# 12v_Outputs.net
KiCad netlist of a schematic drawn in Altium Designer
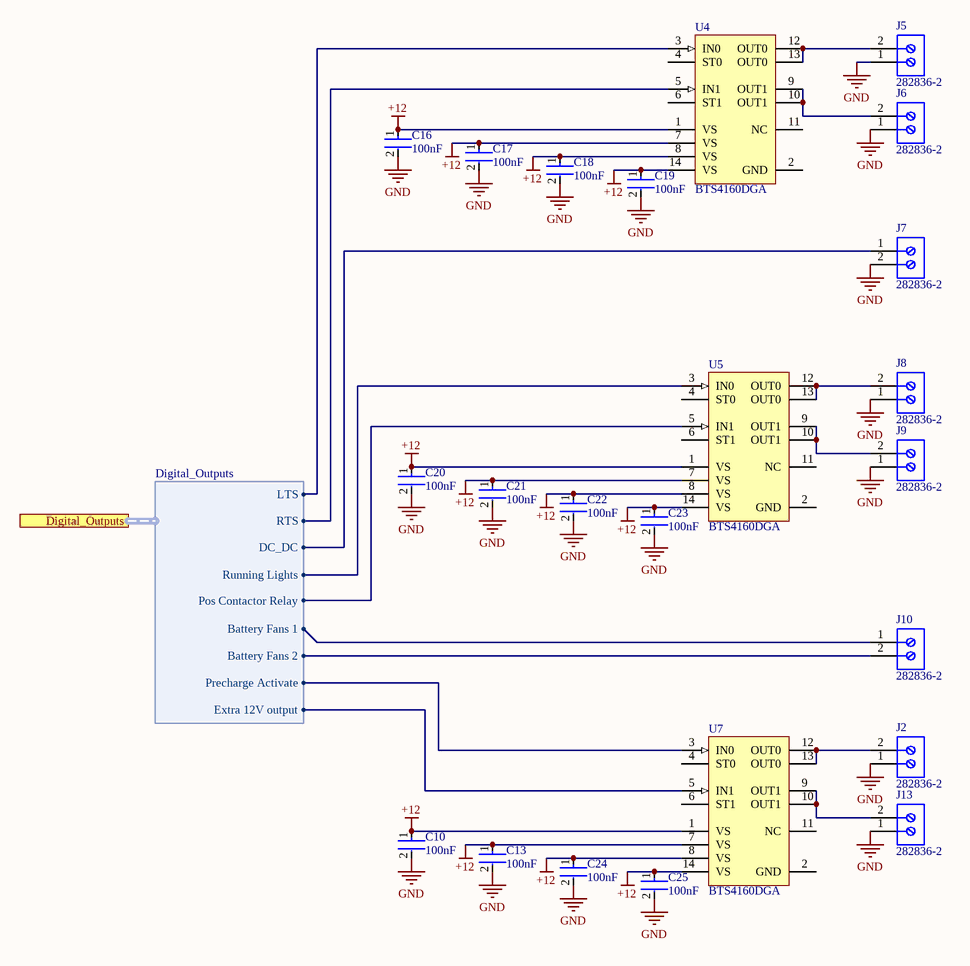
[diagram p0: 12v_Outputs.SchDoc]

(export (version "E")
  (design (tool "Eeschema 10.0.6"))
  (components
    (comp (ref "C10")
      (value "100nF")
      (footprint "Kemet_C0603_IPC_A")
      (description "CAP CER 0.1UF 100NF 50V X7R 0603 C0603C104K5RACTU")
      (libsource (lib "UNK_Kemet_C0603C104K5RACTU_eec") (part "C0603C104K5RACTU"))
    )
    (comp (ref "C13")
      (value "100nF")
      (footprint "Kemet_C0603_IPC_A")
      (description "CAP CER 0.1UF 100NF 50V X7R 0603 C0603C104K5RACTU")
      (libsource (lib "UNK_Kemet_C0603C104K5RACTU_eec") (part "C0603C104K5RACTU"))
    )
    (comp (ref "C16")
      (value "100nF")
      (footprint "Kemet_C0603_IPC_A")
      (description "CAP CER 0.1UF 100NF 50V X7R 0603 C0603C104K5RACTU")
      (libsource (lib "UNK_Kemet_C0603C104K5RACTU_eec") (part "C0603C104K5RACTU"))
    )
    (comp (ref "C17")
      (value "100nF")
      (footprint "Kemet_C0603_IPC_A")
      (description "CAP CER 0.1UF 100NF 50V X7R 0603 C0603C104K5RACTU")
      (libsource (lib "UNK_Kemet_C0603C104K5RACTU_eec") (part "C0603C104K5RACTU"))
    )
    (comp (ref "C18")
      (value "100nF")
      (footprint "Kemet_C0603_IPC_A")
      (description "CAP CER 0.1UF 100NF 50V X7R 0603 C0603C104K5RACTU")
      (libsource (lib "UNK_Kemet_C0603C104K5RACTU_eec") (part "C0603C104K5RACTU"))
    )
    (comp (ref "C19")
      (value "100nF")
      (footprint "Kemet_C0603_IPC_A")
      (description "CAP CER 0.1UF 100NF 50V X7R 0603 C0603C104K5RACTU")
      (libsource (lib "UNK_Kemet_C0603C104K5RACTU_eec") (part "C0603C104K5RACTU"))
    )
    (comp (ref "C20")
      (value "100nF")
      (footprint "Kemet_C0603_IPC_A")
      (description "CAP CER 0.1UF 100NF 50V X7R 0603 C0603C104K5RACTU")
      (libsource (lib "UNK_Kemet_C0603C104K5RACTU_eec") (part "C0603C104K5RACTU"))
    )
    (comp (ref "C21")
      (value "100nF")
      (footprint "Kemet_C0603_IPC_A")
      (description "CAP CER 0.1UF 100NF 50V X7R 0603 C0603C104K5RACTU")
      (libsource (lib "UNK_Kemet_C0603C104K5RACTU_eec") (part "C0603C104K5RACTU"))
    )
    (comp (ref "C22")
      (value "100nF")
      (footprint "Kemet_C0603_IPC_A")
      (description "CAP CER 0.1UF 100NF 50V X7R 0603 C0603C104K5RACTU")
      (libsource (lib "UNK_Kemet_C0603C104K5RACTU_eec") (part "C0603C104K5RACTU"))
    )
    (comp (ref "C23")
      (value "100nF")
      (footprint "Kemet_C0603_IPC_A")
      (description "CAP CER 0.1UF 100NF 50V X7R 0603 C0603C104K5RACTU")
      (libsource (lib "UNK_Kemet_C0603C104K5RACTU_eec") (part "C0603C104K5RACTU"))
    )
    (comp (ref "C24")
      (value "100nF")
      (footprint "Kemet_C0603_IPC_A")
      (description "CAP CER 0.1UF 100NF 50V X7R 0603 C0603C104K5RACTU")
      (libsource (lib "UNK_Kemet_C0603C104K5RACTU_eec") (part "C0603C104K5RACTU"))
    )
    (comp (ref "C25")
      (value "100nF")
      (footprint "Kemet_C0603_IPC_A")
      (description "CAP CER 0.1UF 100NF 50V X7R 0603 C0603C104K5RACTU")
      (libsource (lib "UNK_Kemet_C0603C104K5RACTU_eec") (part "C0603C104K5RACTU"))
    )
    (comp (ref "J2")
      (value "282836-2")
      (footprint "TECO-282836-2_V")
      (description "Female Header, Pitch 5 mm, 1 x 2 Position, Height 10 mm, Tail Length 3.5 mm, Rohs, Bulk")
      (fields (field (name "VOLTAGE") "300V") (field (name "MANUFACTURER") "TE Connectivity"))
      (libsource (lib "Altium Content Vault") (part "CN-1P-F-TB2"))
    )
    (comp (ref "J5")
      (value "282836-2")
      (footprint "TECO-282836-2_V")
      (description "Female Header, Pitch 5 mm, 1 x 2 Position, Height 10 mm, Tail Length 3.5 mm, Rohs, Bulk")
      (fields (field (name "VOLTAGE") "300V") (field (name "MANUFACTURER") "TE Connectivity"))
      (libsource (lib "Altium Content Vault") (part "CN-1P-F-TB2"))
    )
    (comp (ref "J6")
      (value "282836-2")
      (footprint "TECO-282836-2_V")
      (description "Female Header, Pitch 5 mm, 1 x 2 Position, Height 10 mm, Tail Length 3.5 mm, Rohs, Bulk")
      (fields (field (name "VOLTAGE") "300V") (field (name "MANUFACTURER") "TE Connectivity"))
      (libsource (lib "Altium Content Vault") (part "CN-1P-F-TB2"))
    )
    (comp (ref "J7")
      (value "282836-2")
      (footprint "TECO-282836-2_V")
      (description "Female Header, Pitch 5 mm, 1 x 2 Position, Height 10 mm, Tail Length 3.5 mm, Rohs, Bulk")
      (fields (field (name "VOLTAGE") "300V") (field (name "MANUFACTURER") "TE Connectivity"))
      (libsource (lib "Altium Content Vault") (part "CN-1P-F-TB2"))
    )
    (comp (ref "J8")
      (value "282836-2")
      (footprint "TECO-282836-2_V")
      (description "Female Header, Pitch 5 mm, 1 x 2 Position, Height 10 mm, Tail Length 3.5 mm, Rohs, Bulk")
      (fields (field (name "VOLTAGE") "300V") (field (name "MANUFACTURER") "TE Connectivity"))
      (libsource (lib "Altium Content Vault") (part "CN-1P-F-TB2"))
    )
    (comp (ref "J9")
      (value "282836-2")
      (footprint "TECO-282836-2_V")
      (description "Female Header, Pitch 5 mm, 1 x 2 Position, Height 10 mm, Tail Length 3.5 mm, Rohs, Bulk")
      (fields (field (name "VOLTAGE") "300V") (field (name "MANUFACTURER") "TE Connectivity"))
      (libsource (lib "Altium Content Vault") (part "CN-1P-F-TB2"))
    )
    (comp (ref "J10")
      (value "282836-2")
      (footprint "TECO-282836-2_V")
      (description "Female Header, Pitch 5 mm, 1 x 2 Position, Height 10 mm, Tail Length 3.5 mm, Rohs, Bulk")
      (fields (field (name "VOLTAGE") "300V") (field (name "MANUFACTURER") "TE Connectivity"))
      (libsource (lib "Altium Content Vault") (part "CN-1P-F-TB2"))
    )
    (comp (ref "J13")
      (value "282836-2")
      (footprint "TECO-282836-2_V")
      (description "Female Header, Pitch 5 mm, 1 x 2 Position, Height 10 mm, Tail Length 3.5 mm, Rohs, Bulk")
      (fields (field (name "VOLTAGE") "300V") (field (name "MANUFACTURER") "TE Connectivity"))
      (libsource (lib "Altium Content Vault") (part "CN-1P-F-TB2"))
    )
    (comp (ref "U4")
      (value "BTS4160DGA")
      (footprint "INF-PG-DSO-14-37_N")
      (fields (field (name "MANUFACTURER") "Infineon"))
      (libsource (lib "Infineon_BTS4160DGA") (part "BTS4160DGA"))
    )
    (comp (ref "U5")
      (value "BTS4160DGA")
      (footprint "INF-PG-DSO-14-37_N")
      (fields (field (name "MANUFACTURER") "Infineon"))
      (libsource (lib "Infineon_BTS4160DGA") (part "BTS4160DGA"))
    )
    (comp (ref "U7")
      (value "BTS4160DGA")
      (footprint "INF-PG-DSO-14-37_N")
      (fields (field (name "MANUFACTURER") "Infineon"))
      (libsource (lib "Infineon_BTS4160DGA") (part "BTS4160DGA"))
    )
  )
  (nets
    (net (code "2") (name "+12") (class "Default")
      (node (ref "C10") (pin "1") (pinfunction "1_1") (pintype "passive"))
      (node (ref "C13") (pin "1") (pinfunction "1_1") (pintype "passive"))
      (node (ref "C16") (pin "1") (pinfunction "1_1") (pintype "passive"))
      (node (ref "C17") (pin "1") (pinfunction "1_1") (pintype "passive"))
      (node (ref "C18") (pin "1") (pinfunction "1_1") (pintype "passive"))
      (node (ref "C19") (pin "1") (pinfunction "1_1") (pintype "passive"))
      (node (ref "C20") (pin "1") (pinfunction "1_1") (pintype "passive"))
      (node (ref "C21") (pin "1") (pinfunction "1_1") (pintype "passive"))
      (node (ref "C22") (pin "1") (pinfunction "1_1") (pintype "passive"))
      (node (ref "C23") (pin "1") (pinfunction "1_1") (pintype "passive"))
      (node (ref "C24") (pin "1") (pinfunction "1_1") (pintype "passive"))
      (node (ref "C25") (pin "1") (pinfunction "1_1") (pintype "passive"))
      (node (ref "U4") (pin "1") (pinfunction "VS_1") (pintype "power_in"))
      (node (ref "U4") (pin "14") (pinfunction "VS_14") (pintype "power_in"))
      (node (ref "U4") (pin "7") (pinfunction "VS_7") (pintype "power_in"))
      (node (ref "U4") (pin "8") (pinfunction "VS_8") (pintype "power_in"))
      (node (ref "U5") (pin "1") (pinfunction "VS_1") (pintype "power_in"))
      (node (ref "U5") (pin "14") (pinfunction "VS_14") (pintype "power_in"))
      (node (ref "U5") (pin "7") (pinfunction "VS_7") (pintype "power_in"))
      (node (ref "U5") (pin "8") (pinfunction "VS_8") (pintype "power_in"))
      (node (ref "U7") (pin "1") (pinfunction "VS_1") (pintype "power_in"))
      (node (ref "U7") (pin "14") (pinfunction "VS_14") (pintype "power_in"))
      (node (ref "U7") (pin "7") (pinfunction "VS_7") (pintype "power_in"))
      (node (ref "U7") (pin "8") (pinfunction "VS_8") (pintype "power_in"))
    )
    (net (code "3") (name "/Battery Fans 1") (class "Default")
      (node (ref "J10") (pin "1") (pinfunction "1_1") (pintype "passive"))
    )
    (net (code "4") (name "/Battery Fans 2") (class "Default")
      (node (ref "J10") (pin "2") (pinfunction "2_2") (pintype "passive"))
    )
    (net (code "5") (name "/DC_DC") (class "Default")
      (node (ref "J7") (pin "1") (pinfunction "1_1") (pintype "passive"))
    )
    (net (code "6") (name "/Extra 12V output") (class "Default")
      (node (ref "U7") (pin "5") (pinfunction "IN1_5") (pintype "input"))
    )
    (net (code "7") (name "/LTS") (class "Default")
      (node (ref "U4") (pin "3") (pinfunction "IN0_3") (pintype "input"))
    )
    (net (code "8") (name "/Pos Contactor Relay") (class "Default")
      (node (ref "U5") (pin "5") (pinfunction "IN1_5") (pintype "input"))
    )
    (net (code "9") (name "/Precharge Activate") (class "Default")
      (node (ref "U7") (pin "3") (pinfunction "IN0_3") (pintype "input"))
    )
    (net (code "10") (name "/RTS") (class "Default")
      (node (ref "U4") (pin "5") (pinfunction "IN1_5") (pintype "input"))
    )
    (net (code "11") (name "/Running Lights") (class "Default")
      (node (ref "U5") (pin "3") (pinfunction "IN0_3") (pintype "input"))
    )
    (net (code "13") (name "GND") (class "Default")
      (node (ref "C10") (pin "2") (pinfunction "2_2") (pintype "passive"))
      (node (ref "C13") (pin "2") (pinfunction "2_2") (pintype "passive"))
      (node (ref "C16") (pin "2") (pinfunction "2_2") (pintype "passive"))
      (node (ref "C17") (pin "2") (pinfunction "2_2") (pintype "passive"))
      (node (ref "C18") (pin "2") (pinfunction "2_2") (pintype "passive"))
      (node (ref "C19") (pin "2") (pinfunction "2_2") (pintype "passive"))
      (node (ref "C20") (pin "2") (pinfunction "2_2") (pintype "passive"))
      (node (ref "C21") (pin "2") (pinfunction "2_2") (pintype "passive"))
      (node (ref "C22") (pin "2") (pinfunction "2_2") (pintype "passive"))
      (node (ref "C23") (pin "2") (pinfunction "2_2") (pintype "passive"))
      (node (ref "C24") (pin "2") (pinfunction "2_2") (pintype "passive"))
      (node (ref "C25") (pin "2") (pinfunction "2_2") (pintype "passive"))
      (node (ref "J13") (pin "1") (pinfunction "1_1") (pintype "passive"))
      (node (ref "J2") (pin "1") (pinfunction "1_1") (pintype "passive"))
      (node (ref "J5") (pin "1") (pinfunction "1_1") (pintype "passive"))
      (node (ref "J6") (pin "1") (pinfunction "1_1") (pintype "passive"))
      (node (ref "J7") (pin "2") (pinfunction "2_2") (pintype "passive"))
      (node (ref "J8") (pin "1") (pinfunction "1_1") (pintype "passive"))
      (node (ref "J9") (pin "1") (pinfunction "1_1") (pintype "passive"))
    )
    (net (code "14") (name "Net-(J2-Pad2)") (class "Default")
      (node (ref "J2") (pin "2") (pinfunction "2_2") (pintype "passive"))
      (node (ref "U7") (pin "12") (pinfunction "OUT0_12") (pintype "power_in"))
      (node (ref "U7") (pin "13") (pinfunction "OUT0_13") (pintype "power_in"))
    )
    (net (code "15") (name "Net-(J5-Pad2)") (class "Default")
      (node (ref "J5") (pin "2") (pinfunction "2_2") (pintype "passive"))
      (node (ref "U4") (pin "12") (pinfunction "OUT0_12") (pintype "power_in"))
      (node (ref "U4") (pin "13") (pinfunction "OUT0_13") (pintype "power_in"))
    )
    (net (code "16") (name "Net-(J6-Pad2)") (class "Default")
      (node (ref "J6") (pin "2") (pinfunction "2_2") (pintype "passive"))
      (node (ref "U4") (pin "10") (pinfunction "OUT1_10") (pintype "power_in"))
      (node (ref "U4") (pin "9") (pinfunction "OUT1_9") (pintype "power_in"))
    )
    (net (code "17") (name "Net-(J8-Pad2)") (class "Default")
      (node (ref "J8") (pin "2") (pinfunction "2_2") (pintype "passive"))
      (node (ref "U5") (pin "12") (pinfunction "OUT0_12") (pintype "power_in"))
      (node (ref "U5") (pin "13") (pinfunction "OUT0_13") (pintype "power_in"))
    )
    (net (code "18") (name "Net-(J9-Pad2)") (class "Default")
      (node (ref "J9") (pin "2") (pinfunction "2_2") (pintype "passive"))
      (node (ref "U5") (pin "10") (pinfunction "OUT1_10") (pintype "power_in"))
      (node (ref "U5") (pin "9") (pinfunction "OUT1_9") (pintype "power_in"))
    )
    (net (code "19") (name "Net-(J13-Pad2)") (class "Default")
      (node (ref "J13") (pin "2") (pinfunction "2_2") (pintype "passive"))
      (node (ref "U7") (pin "10") (pinfunction "OUT1_10") (pintype "power_in"))
      (node (ref "U7") (pin "9") (pinfunction "OUT1_9") (pintype "power_in"))
    )
    (net (code "20") (name "unconnected-(U4-GND-Pad2)") (class "Default")
      (node (ref "U4") (pin "2") (pinfunction "GND_2") (pintype "power_in"))
    )
    (net (code "21") (name "unconnected-(U4-NC-Pad11)") (class "Default")
      (node (ref "U4") (pin "11") (pinfunction "NC_11") (pintype "passive"))
    )
    (net (code "22") (name "unconnected-(U4-ST0-Pad4)") (class "Default")
      (node (ref "U4") (pin "4") (pinfunction "ST0_4") (pintype "open_collector"))
    )
    (net (code "23") (name "unconnected-(U4-ST1-Pad6)") (class "Default")
      (node (ref "U4") (pin "6") (pinfunction "ST1_6") (pintype "open_collector"))
    )
    (net (code "24") (name "unconnected-(U5-GND-Pad2)") (class "Default")
      (node (ref "U5") (pin "2") (pinfunction "GND_2") (pintype "power_in"))
    )
    (net (code "25") (name "unconnected-(U5-NC-Pad11)") (class "Default")
      (node (ref "U5") (pin "11") (pinfunction "NC_11") (pintype "passive"))
    )
    (net (code "26") (name "unconnected-(U5-ST0-Pad4)") (class "Default")
      (node (ref "U5") (pin "4") (pinfunction "ST0_4") (pintype "open_collector"))
    )
    (net (code "27") (name "unconnected-(U5-ST1-Pad6)") (class "Default")
      (node (ref "U5") (pin "6") (pinfunction "ST1_6") (pintype "open_collector"))
    )
    (net (code "28") (name "unconnected-(U7-GND-Pad2)") (class "Default")
      (node (ref "U7") (pin "2") (pinfunction "GND_2") (pintype "power_in"))
    )
    (net (code "29") (name "unconnected-(U7-NC-Pad11)") (class "Default")
      (node (ref "U7") (pin "11") (pinfunction "NC_11") (pintype "passive"))
    )
    (net (code "30") (name "unconnected-(U7-ST0-Pad4)") (class "Default")
      (node (ref "U7") (pin "4") (pinfunction "ST0_4") (pintype "open_collector"))
    )
    (net (code "31") (name "unconnected-(U7-ST1-Pad6)") (class "Default")
      (node (ref "U7") (pin "6") (pinfunction "ST1_6") (pintype "open_collector"))
    )
  )
)
